# haasoscope_pro_clock_board.net
KiCad netlist of a schematic drawn in EAGLE
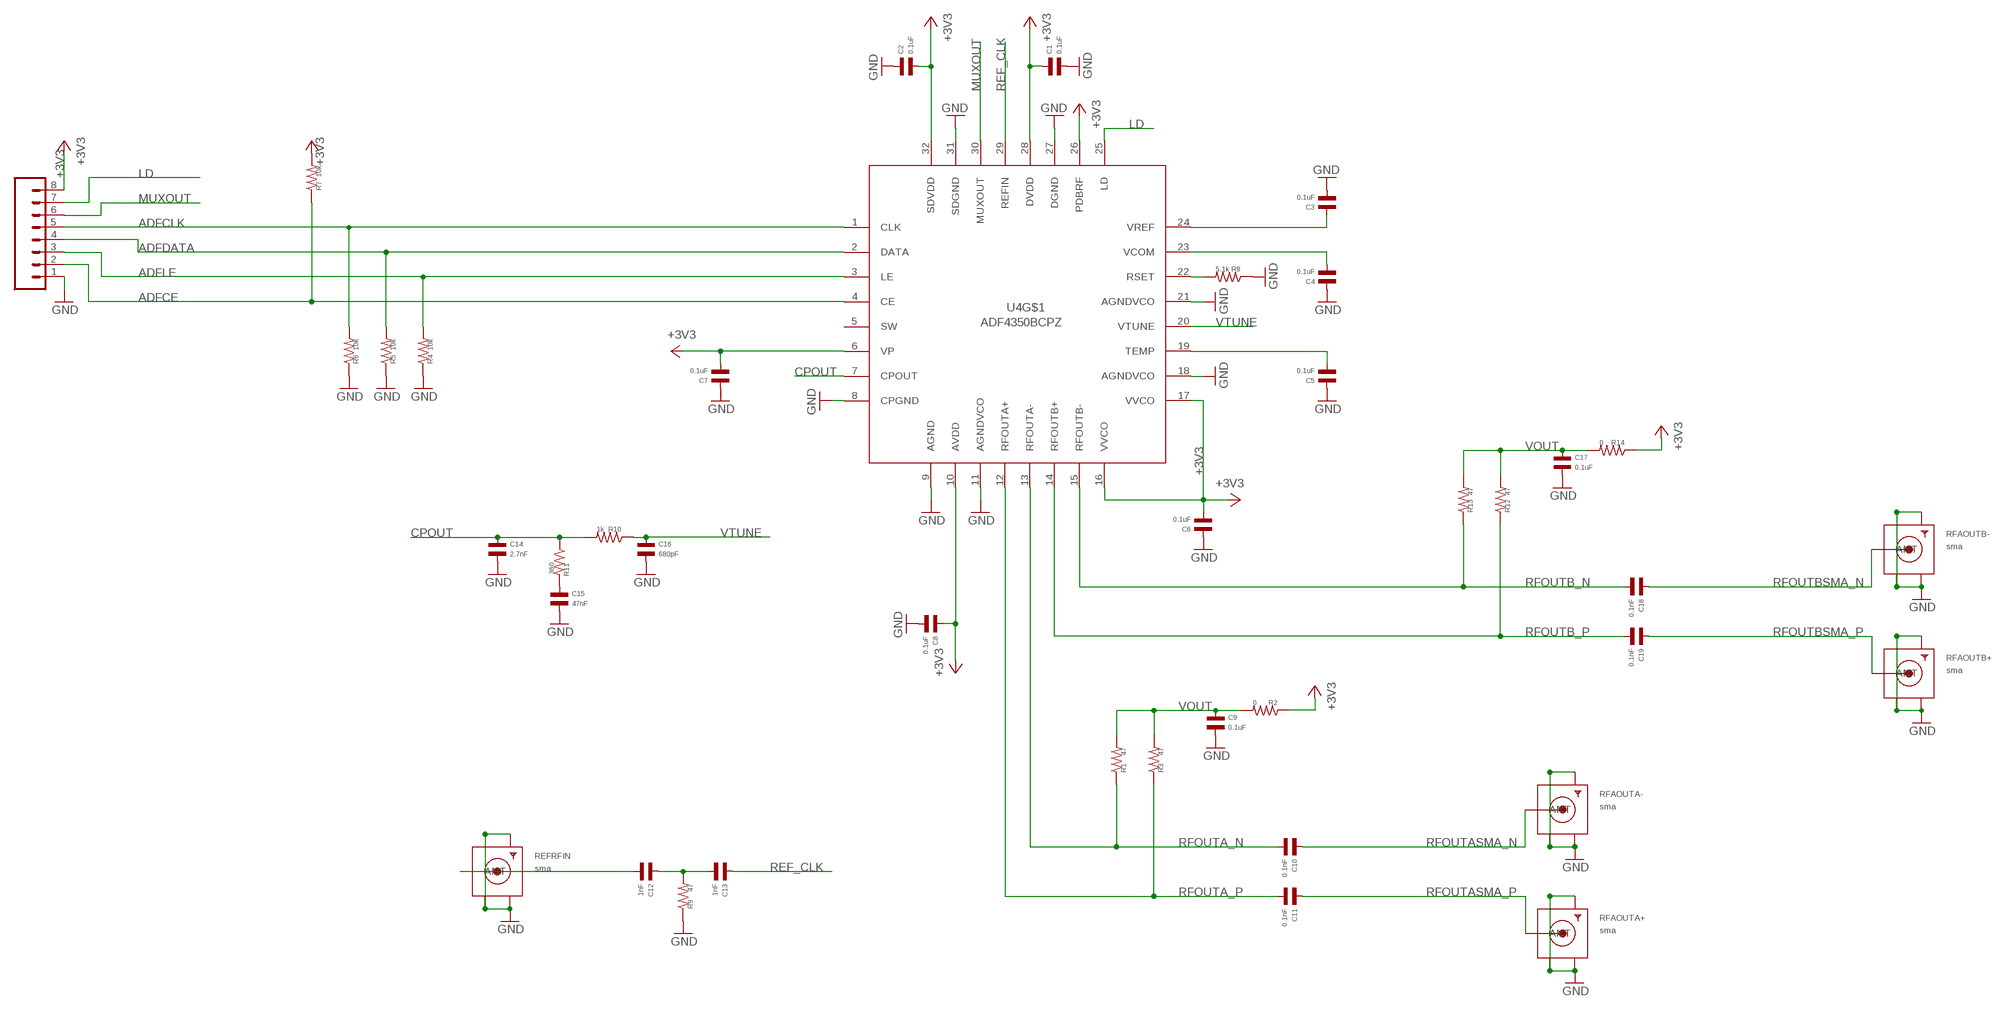
[diagram p0: schematic, sheet 1]

(export (version "E")
  (design (tool "Eeschema 10.0.6"))
  (components
    (comp (ref "C1")
      (value "0.1uF")
      (footprint "eagle-import:C0402")
      (libsource (lib "eagle-import") (part "CAPACITOR_NP_0402"))
    )
    (comp (ref "C2")
      (value "0.1uF")
      (footprint "eagle-import:C0402")
      (libsource (lib "eagle-import") (part "CAPACITOR_NP_0402"))
    )
    (comp (ref "C3")
      (value "0.1uF")
      (footprint "eagle-import:C0402")
      (libsource (lib "eagle-import") (part "CAPACITOR_NP_0402"))
    )
    (comp (ref "C4")
      (value "0.1uF")
      (footprint "eagle-import:C0402")
      (libsource (lib "eagle-import") (part "CAPACITOR_NP_0402"))
    )
    (comp (ref "C5")
      (value "0.1uF")
      (footprint "eagle-import:C0402")
      (libsource (lib "eagle-import") (part "CAPACITOR_NP_0402"))
    )
    (comp (ref "C6")
      (value "0.1uF")
      (footprint "eagle-import:C0402")
      (libsource (lib "eagle-import") (part "CAPACITOR_NP_0402"))
    )
    (comp (ref "C7")
      (value "0.1uF")
      (footprint "eagle-import:C0402")
      (libsource (lib "eagle-import") (part "CAPACITOR_NP_0402"))
    )
    (comp (ref "C8")
      (value "0.1uF")
      (footprint "eagle-import:C0402")
      (libsource (lib "eagle-import") (part "CAPACITOR_NP_0402"))
    )
    (comp (ref "C9")
      (value "0.1uF")
      (footprint "eagle-import:C0402")
      (libsource (lib "eagle-import") (part "CAPACITOR_NP_0402"))
    )
    (comp (ref "C10")
      (value "0.1nF")
      (footprint "eagle-import:C0402")
      (libsource (lib "eagle-import") (part "CAPACITOR_NP_0402"))
    )
    (comp (ref "C11")
      (value "0.1nF")
      (footprint "eagle-import:C0402")
      (libsource (lib "eagle-import") (part "CAPACITOR_NP_0402"))
    )
    (comp (ref "C12")
      (value "1nF")
      (footprint "eagle-import:C0402")
      (libsource (lib "eagle-import") (part "CAPACITOR_NP_0402"))
    )
    (comp (ref "C13")
      (value "1nF")
      (footprint "eagle-import:C0402")
      (libsource (lib "eagle-import") (part "CAPACITOR_NP_0402"))
    )
    (comp (ref "C14")
      (value "2.7nF")
      (footprint "eagle-import:C0402")
      (libsource (lib "eagle-import") (part "CAPACITOR_NP_0402"))
    )
    (comp (ref "C15")
      (value "47nF")
      (footprint "eagle-import:C0402")
      (libsource (lib "eagle-import") (part "CAPACITOR_NP_0402"))
    )
    (comp (ref "C16")
      (value "680pF")
      (footprint "eagle-import:C0402")
      (libsource (lib "eagle-import") (part "CAPACITOR_NP_0402"))
    )
    (comp (ref "C17")
      (value "0.1uF")
      (footprint "eagle-import:C0402")
      (libsource (lib "eagle-import") (part "CAPACITOR_NP_0402"))
    )
    (comp (ref "C18")
      (value "0.1nF")
      (footprint "eagle-import:C0402")
      (libsource (lib "eagle-import") (part "CAPACITOR_NP_0402"))
    )
    (comp (ref "C19")
      (value "0.1nF")
      (footprint "eagle-import:C0402")
      (libsource (lib "eagle-import") (part "CAPACITOR_NP_0402"))
    )
    (comp (ref "J4")
      (value "8pin")
      (footprint "eagle-import:1X08")
      (libsource (lib "eagle-import") (part "CONN_08{dblquote}"))
    )
    (comp (ref "R1")
      (value "47")
      (footprint "eagle-import:R0402")
      (libsource (lib "eagle-import") (part "RESISTOR_0402"))
    )
    (comp (ref "R2")
      (value "0")
      (footprint "eagle-import:R0402")
      (libsource (lib "eagle-import") (part "RESISTOR_0402"))
    )
    (comp (ref "R3")
      (value "47")
      (footprint "eagle-import:R0402")
      (libsource (lib "eagle-import") (part "RESISTOR_0402"))
    )
    (comp (ref "R4")
      (value "10k")
      (footprint "eagle-import:R0402")
      (libsource (lib "eagle-import") (part "RESISTOR_0402"))
    )
    (comp (ref "R5")
      (value "10k")
      (footprint "eagle-import:R0402")
      (libsource (lib "eagle-import") (part "RESISTOR_0402"))
    )
    (comp (ref "R6")
      (value "10k")
      (footprint "eagle-import:R0402")
      (libsource (lib "eagle-import") (part "RESISTOR_0402"))
    )
    (comp (ref "R7")
      (value "10k")
      (footprint "eagle-import:R0402")
      (libsource (lib "eagle-import") (part "RESISTOR_0402"))
    )
    (comp (ref "R8")
      (value "5.1k")
      (footprint "eagle-import:R0402")
      (libsource (lib "eagle-import") (part "RESISTOR_0402"))
    )
    (comp (ref "R9")
      (value "47")
      (footprint "eagle-import:R0402")
      (libsource (lib "eagle-import") (part "RESISTOR_0402"))
    )
    (comp (ref "R10")
      (value "1k")
      (footprint "eagle-import:R0402")
      (libsource (lib "eagle-import") (part "RESISTOR_0402"))
    )
    (comp (ref "R11")
      (value "360")
      (footprint "eagle-import:R0402")
      (libsource (lib "eagle-import") (part "RESISTOR_0402"))
    )
    (comp (ref "R12")
      (value "47")
      (footprint "eagle-import:R0402")
      (libsource (lib "eagle-import") (part "RESISTOR_0402"))
    )
    (comp (ref "R13")
      (value "47")
      (footprint "eagle-import:R0402")
      (libsource (lib "eagle-import") (part "RESISTOR_0402"))
    )
    (comp (ref "R14")
      (value "0")
      (footprint "eagle-import:R0402")
      (libsource (lib "eagle-import") (part "RESISTOR_0402"))
    )
    (comp (ref "REFRFIN")
      (value "sma")
      (footprint "eagle-import:SMA_EDGELAUNCH")
      (libsource (lib "eagle-import") (part "SMACONNECTOR_EDGE"))
    )
    (comp (ref "RFAOUTA+")
      (value "sma")
      (footprint "eagle-import:SMA_EDGELAUNCH")
      (libsource (lib "eagle-import") (part "SMACONNECTOR_EDGE"))
    )
    (comp (ref "RFAOUTA-")
      (value "sma")
      (footprint "eagle-import:SMA_EDGELAUNCH")
      (libsource (lib "eagle-import") (part "SMACONNECTOR_EDGE"))
    )
    (comp (ref "RFAOUTB+")
      (value "sma")
      (footprint "eagle-import:SMA_EDGELAUNCH")
      (libsource (lib "eagle-import") (part "SMACONNECTOR_EDGE"))
    )
    (comp (ref "RFAOUTB-")
      (value "sma")
      (footprint "eagle-import:SMA_EDGELAUNCH")
      (libsource (lib "eagle-import") (part "SMACONNECTOR_EDGE"))
    )
    (comp (ref "U4")
      (value "ADF4350BCPZ")
      (footprint "eagle-import:QFN50P500X500X100-33V2N")
      (libsource (lib "eagle-import") (part "ADF4350BCPZ"))
    )
  )
  (nets
    (net (code "1") (name "+3V3") (class "Default")
      (node (ref "C1") (pin "P$1") (pinfunction "P$1_P$1") (pintype "passive"))
      (node (ref "C2") (pin "P$2") (pinfunction "P$2_P$2") (pintype "passive"))
      (node (ref "C6") (pin "P$2") (pinfunction "P$2_P$2") (pintype "passive"))
      (node (ref "C7") (pin "P$2") (pinfunction "P$2_P$2") (pintype "passive"))
      (node (ref "C8") (pin "P$1") (pinfunction "P$1_P$1") (pintype "passive"))
      (node (ref "J4") (pin "8") (pinfunction "8_8") (pintype "passive"))
      (node (ref "R14") (pin "P$1") (pinfunction "P$1_P$1") (pintype "passive"))
      (node (ref "R2") (pin "P$1") (pinfunction "P$1_P$1") (pintype "passive"))
      (node (ref "R7") (pin "P$2") (pinfunction "P$2_P$2") (pintype "passive"))
      (node (ref "U4") (pin "10") (pinfunction "AVDD_10") (pintype "power_in"))
      (node (ref "U4") (pin "16") (pinfunction "VVCO_16") (pintype "power_in"))
      (node (ref "U4") (pin "17") (pinfunction "VVCO_17") (pintype "power_in"))
      (node (ref "U4") (pin "26") (pinfunction "PDBRF_26") (pintype "input"))
      (node (ref "U4") (pin "28") (pinfunction "DVDD_28") (pintype "power_in"))
      (node (ref "U4") (pin "32") (pinfunction "SDVDD_32") (pintype "power_in"))
      (node (ref "U4") (pin "6") (pinfunction "VP_6") (pintype "power_in"))
    )
    (net (code "2") (name "/ADFCE") (class "Default")
      (node (ref "J4") (pin "2") (pinfunction "2_2") (pintype "passive"))
      (node (ref "R7") (pin "P$1") (pinfunction "P$1_P$1") (pintype "passive"))
      (node (ref "U4") (pin "4") (pinfunction "CE_4") (pintype "input"))
    )
    (net (code "3") (name "/ADFCLK") (class "Default")
      (node (ref "J4") (pin "5") (pinfunction "5_5") (pintype "passive"))
      (node (ref "R6") (pin "P$2") (pinfunction "P$2_P$2") (pintype "passive"))
      (node (ref "U4") (pin "1") (pinfunction "CLK_1") (pintype "input"))
    )
    (net (code "4") (name "/ADFDATA") (class "Default")
      (node (ref "J4") (pin "4") (pinfunction "4_4") (pintype "passive"))
      (node (ref "R5") (pin "P$2") (pinfunction "P$2_P$2") (pintype "passive"))
      (node (ref "U4") (pin "2") (pinfunction "DATA_2") (pintype "input"))
    )
    (net (code "5") (name "/ADFLE") (class "Default")
      (node (ref "J4") (pin "3") (pinfunction "3_3") (pintype "passive"))
      (node (ref "R4") (pin "P$2") (pinfunction "P$2_P$2") (pintype "passive"))
      (node (ref "U4") (pin "3") (pinfunction "LE_3") (pintype "input"))
    )
    (net (code "6") (name "/CPOUT") (class "Default")
      (node (ref "C14") (pin "P$1") (pinfunction "P$1_P$1") (pintype "passive"))
      (node (ref "R10") (pin "P$2") (pinfunction "P$2_P$2") (pintype "passive"))
      (node (ref "R11") (pin "P$1") (pinfunction "P$1_P$1") (pintype "passive"))
      (node (ref "U4") (pin "7") (pinfunction "CPOUT_7") (pintype "output"))
    )
    (net (code "7") (name "/LD") (class "Default")
      (node (ref "J4") (pin "7") (pinfunction "7_7") (pintype "passive"))
      (node (ref "U4") (pin "25") (pinfunction "LD_25") (pintype "output"))
    )
    (net (code "8") (name "/MUXOUT") (class "Default")
      (node (ref "J4") (pin "6") (pinfunction "6_6") (pintype "passive"))
      (node (ref "U4") (pin "30") (pinfunction "MUXOUT_30") (pintype "output"))
    )
    (net (code "9") (name "/REF_CLK") (class "Default")
      (node (ref "C13") (pin "P$1") (pinfunction "P$1_P$1") (pintype "passive"))
      (node (ref "U4") (pin "29") (pinfunction "REFIN_29") (pintype "input"))
    )
    (net (code "10") (name "/RFOUTASMA_N") (class "Default")
      (node (ref "C10") (pin "P$1") (pinfunction "P$1_P$1") (pintype "passive"))
      (node (ref "RFAOUTA-") (pin "P") (pinfunction "ANT_P") (pintype "bidirectional"))
    )
    (net (code "11") (name "/RFOUTASMA_P") (class "Default")
      (node (ref "C11") (pin "P$1") (pinfunction "P$1_P$1") (pintype "passive"))
      (node (ref "RFAOUTA+") (pin "P") (pinfunction "ANT_P") (pintype "bidirectional"))
    )
    (net (code "12") (name "/RFOUTA_N") (class "Default")
      (node (ref "C10") (pin "P$2") (pinfunction "P$2_P$2") (pintype "passive"))
      (node (ref "R1") (pin "P$1") (pinfunction "P$1_P$1") (pintype "passive"))
      (node (ref "U4") (pin "13") (pinfunction "RFOUTA-_13") (pintype "output"))
    )
    (net (code "13") (name "/RFOUTA_P") (class "Default")
      (node (ref "C11") (pin "P$2") (pinfunction "P$2_P$2") (pintype "passive"))
      (node (ref "R3") (pin "P$1") (pinfunction "P$1_P$1") (pintype "passive"))
      (node (ref "U4") (pin "12") (pinfunction "RFOUTA+_12") (pintype "output"))
    )
    (net (code "14") (name "/RFOUTBSMA_N") (class "Default")
      (node (ref "C18") (pin "P$1") (pinfunction "P$1_P$1") (pintype "passive"))
      (node (ref "RFAOUTB-") (pin "P") (pinfunction "ANT_P") (pintype "bidirectional"))
    )
    (net (code "15") (name "/RFOUTBSMA_P") (class "Default")
      (node (ref "C19") (pin "P$1") (pinfunction "P$1_P$1") (pintype "passive"))
      (node (ref "RFAOUTB+") (pin "P") (pinfunction "ANT_P") (pintype "bidirectional"))
    )
    (net (code "16") (name "/RFOUTB_N") (class "Default")
      (node (ref "C18") (pin "P$2") (pinfunction "P$2_P$2") (pintype "passive"))
      (node (ref "R13") (pin "P$1") (pinfunction "P$1_P$1") (pintype "passive"))
      (node (ref "U4") (pin "15") (pinfunction "RFOUTB-_15") (pintype "output"))
    )
    (net (code "17") (name "/RFOUTB_P") (class "Default")
      (node (ref "C19") (pin "P$2") (pinfunction "P$2_P$2") (pintype "passive"))
      (node (ref "R12") (pin "P$1") (pinfunction "P$1_P$1") (pintype "passive"))
      (node (ref "U4") (pin "14") (pinfunction "RFOUTB+_14") (pintype "output"))
    )
    (net (code "18") (name "/VOUT") (class "Default")
      (node (ref "C17") (pin "P$1") (pinfunction "P$1_P$1") (pintype "passive"))
      (node (ref "C9") (pin "P$1") (pinfunction "P$1_P$1") (pintype "passive"))
      (node (ref "R1") (pin "P$2") (pinfunction "P$2_P$2") (pintype "passive"))
      (node (ref "R12") (pin "P$2") (pinfunction "P$2_P$2") (pintype "passive"))
      (node (ref "R13") (pin "P$2") (pinfunction "P$2_P$2") (pintype "passive"))
      (node (ref "R14") (pin "P$2") (pinfunction "P$2_P$2") (pintype "passive"))
      (node (ref "R2") (pin "P$2") (pinfunction "P$2_P$2") (pintype "passive"))
      (node (ref "R3") (pin "P$2") (pinfunction "P$2_P$2") (pintype "passive"))
    )
    (net (code "19") (name "/VTUNE") (class "Default")
      (node (ref "C16") (pin "P$1") (pinfunction "P$1_P$1") (pintype "passive"))
      (node (ref "R10") (pin "P$1") (pinfunction "P$1_P$1") (pintype "passive"))
      (node (ref "U4") (pin "20") (pinfunction "VTUNE_20") (pintype "input"))
    )
    (net (code "20") (name "GND") (class "Default")
      (node (ref "C1") (pin "P$2") (pinfunction "P$2_P$2") (pintype "passive"))
      (node (ref "C14") (pin "P$2") (pinfunction "P$2_P$2") (pintype "passive"))
      (node (ref "C15") (pin "P$2") (pinfunction "P$2_P$2") (pintype "passive"))
      (node (ref "C16") (pin "P$2") (pinfunction "P$2_P$2") (pintype "passive"))
      (node (ref "C17") (pin "P$2") (pinfunction "P$2_P$2") (pintype "passive"))
      (node (ref "C2") (pin "P$1") (pinfunction "P$1_P$1") (pintype "passive"))
      (node (ref "C3") (pin "P$2") (pinfunction "P$2_P$2") (pintype "passive"))
      (node (ref "C4") (pin "P$1") (pinfunction "P$1_P$1") (pintype "passive"))
      (node (ref "C5") (pin "P$1") (pinfunction "P$1_P$1") (pintype "passive"))
      (node (ref "C6") (pin "P$1") (pinfunction "P$1_P$1") (pintype "passive"))
      (node (ref "C7") (pin "P$1") (pinfunction "P$1_P$1") (pintype "passive"))
      (node (ref "C8") (pin "P$2") (pinfunction "P$2_P$2") (pintype "passive"))
      (node (ref "C9") (pin "P$2") (pinfunction "P$2_P$2") (pintype "passive"))
      (node (ref "J4") (pin "1") (pinfunction "1_1") (pintype "passive"))
      (node (ref "R4") (pin "P$1") (pinfunction "P$1_P$1") (pintype "passive"))
      (node (ref "R5") (pin "P$1") (pinfunction "P$1_P$1") (pintype "passive"))
      (node (ref "R6") (pin "P$1") (pinfunction "P$1_P$1") (pintype "passive"))
      (node (ref "R8") (pin "P$1") (pinfunction "P$1_P$1") (pintype "passive"))
      (node (ref "R9") (pin "P$1") (pinfunction "P$1_P$1") (pintype "passive"))
      (node (ref "REFRFIN") (pin "GND@1") (pinfunction "GND4_GND@1") (pintype "power_in"))
      (node (ref "REFRFIN") (pin "GND@2") (pinfunction "GND3_GND@2") (pintype "power_in"))
      (node (ref "REFRFIN") (pin "GND@3") (pinfunction "GND2_GND@3") (pintype "power_in"))
      (node (ref "REFRFIN") (pin "GND@4") (pinfunction "GND1_GND@4") (pintype "power_in"))
      (node (ref "RFAOUTA+") (pin "GND@1") (pinfunction "GND4_GND@1") (pintype "power_in"))
      (node (ref "RFAOUTA+") (pin "GND@2") (pinfunction "GND3_GND@2") (pintype "power_in"))
      (node (ref "RFAOUTA+") (pin "GND@3") (pinfunction "GND2_GND@3") (pintype "power_in"))
      (node (ref "RFAOUTA+") (pin "GND@4") (pinfunction "GND1_GND@4") (pintype "power_in"))
      (node (ref "RFAOUTA-") (pin "GND@1") (pinfunction "GND4_GND@1") (pintype "power_in"))
      (node (ref "RFAOUTA-") (pin "GND@2") (pinfunction "GND3_GND@2") (pintype "power_in"))
      (node (ref "RFAOUTA-") (pin "GND@3") (pinfunction "GND2_GND@3") (pintype "power_in"))
      (node (ref "RFAOUTA-") (pin "GND@4") (pinfunction "GND1_GND@4") (pintype "power_in"))
      (node (ref "RFAOUTB+") (pin "GND@1") (pinfunction "GND4_GND@1") (pintype "power_in"))
      (node (ref "RFAOUTB+") (pin "GND@2") (pinfunction "GND3_GND@2") (pintype "power_in"))
      (node (ref "RFAOUTB+") (pin "GND@3") (pinfunction "GND2_GND@3") (pintype "power_in"))
      (node (ref "RFAOUTB+") (pin "GND@4") (pinfunction "GND1_GND@4") (pintype "power_in"))
      (node (ref "RFAOUTB-") (pin "GND@1") (pinfunction "GND4_GND@1") (pintype "power_in"))
      (node (ref "RFAOUTB-") (pin "GND@2") (pinfunction "GND3_GND@2") (pintype "power_in"))
      (node (ref "RFAOUTB-") (pin "GND@3") (pinfunction "GND2_GND@3") (pintype "power_in"))
      (node (ref "RFAOUTB-") (pin "GND@4") (pinfunction "GND1_GND@4") (pintype "power_in"))
      (node (ref "U4") (pin "11") (pinfunction "AGNDVCO_11") (pintype "power_in"))
      (node (ref "U4") (pin "18") (pinfunction "AGNDVCO_18") (pintype "power_in"))
      (node (ref "U4") (pin "21") (pinfunction "AGNDVCO_21") (pintype "power_in"))
      (node (ref "U4") (pin "27") (pinfunction "DGND_27") (pintype "power_in"))
      (node (ref "U4") (pin "31") (pinfunction "SDGND_31") (pintype "power_in"))
      (node (ref "U4") (pin "8") (pinfunction "CPGND_8") (pintype "power_in"))
      (node (ref "U4") (pin "9") (pinfunction "AGND_9") (pintype "power_in"))
    )
    (net (code "21") (name "Net-(C12-PadP$1)") (class "Default")
      (node (ref "C12") (pin "P$1") (pinfunction "P$1_P$1") (pintype "passive"))
      (node (ref "C13") (pin "P$2") (pinfunction "P$2_P$2") (pintype "passive"))
      (node (ref "R9") (pin "P$2") (pinfunction "P$2_P$2") (pintype "passive"))
    )
    (net (code "22") (name "Net-(C15-PadP$1)") (class "Default")
      (node (ref "C15") (pin "P$1") (pinfunction "P$1_P$1") (pintype "passive"))
      (node (ref "R11") (pin "P$2") (pinfunction "P$2_P$2") (pintype "passive"))
    )
    (net (code "23") (name "Net-(REFRFIN-ANT)") (class "Default")
      (node (ref "C12") (pin "P$2") (pinfunction "P$2_P$2") (pintype "passive"))
      (node (ref "REFRFIN") (pin "P") (pinfunction "ANT_P") (pintype "bidirectional"))
    )
    (net (code "24") (name "Net-(U4A-RSET)") (class "Default")
      (node (ref "R8") (pin "P$2") (pinfunction "P$2_P$2") (pintype "passive"))
      (node (ref "U4") (pin "22") (pinfunction "RSET_22") (pintype "input"))
    )
    (net (code "25") (name "Net-(U4A-TEMP)") (class "Default")
      (node (ref "C5") (pin "P$2") (pinfunction "P$2_P$2") (pintype "passive"))
      (node (ref "U4") (pin "19") (pinfunction "TEMP_19") (pintype "output"))
    )
    (net (code "26") (name "Net-(U4A-VCOM)") (class "Default")
      (node (ref "C4") (pin "P$2") (pinfunction "P$2_P$2") (pintype "passive"))
      (node (ref "U4") (pin "23") (pinfunction "VCOM_23") (pintype "output"))
    )
    (net (code "27") (name "Net-(U4A-VREF)") (class "Default")
      (node (ref "C3") (pin "P$1") (pinfunction "P$1_P$1") (pintype "passive"))
      (node (ref "U4") (pin "24") (pinfunction "VREF_24") (pintype "output"))
    )
    (net (code "28") (name "unconnected-(U4A-SW-Pad5)") (class "Default")
      (node (ref "U4") (pin "5") (pinfunction "SW_5") (pintype "input"))
    )
  )
)
